# pca10040_sheet5_power_supply.net
KiCad netlist of a schematic drawn in Altium Designer
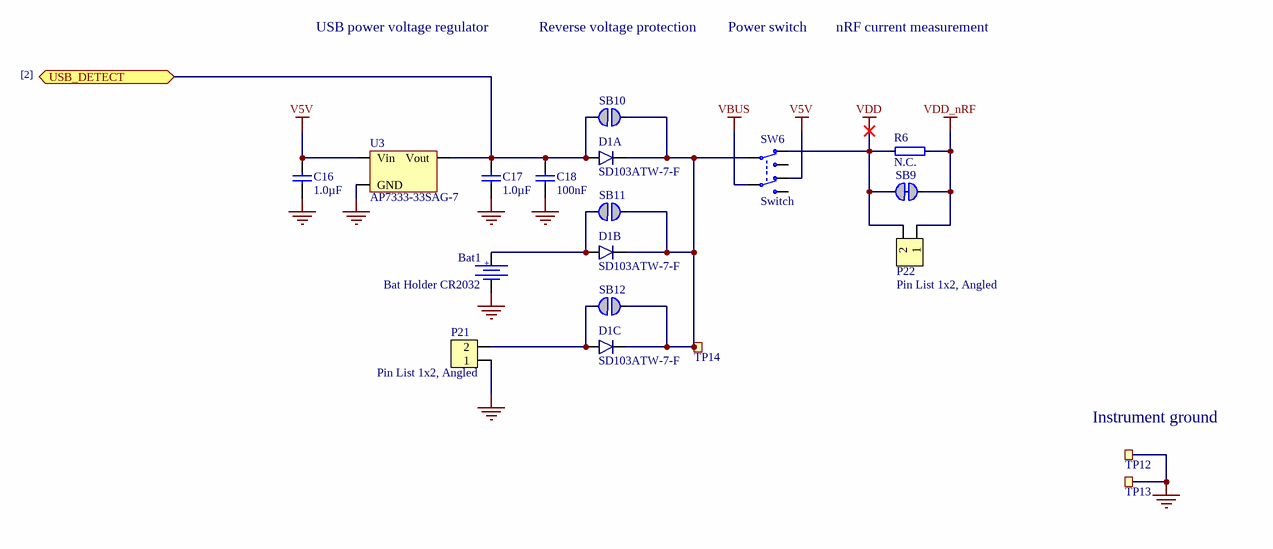
[diagram p0: pca10040_sheet5_power_supply.SchDoc]

(export (version "E")
  (design (tool "Eeschema 10.0.6"))
  (components
    (comp (ref "Bat1")
      (value "Bat Holder CR2032")
      (footprint "CR2032_HOLDER_SMD")
      (description "Bat Holder CR2032 SMD")
      (fields
        (field (name "MANUFACTURER") "Comfortable")
        (field (name "MANUFACTURER PART NUMBER") "BC-2001")
        (field (name "PUBLISHER") "Nordic Semiconductor")
      )
      (libsource (lib "Nordic Passive DB") (part "Battery"))
    )
    (comp (ref "C16")
      (value "1.0µF")
      (footprint "CAPC1608X06L")
      (description "Capacitor, X7R, ±10%")
      (fields (field (name "PART NUMBER") "C0603-1µ0") (field (name "PUBLISHER") "Nordic Semiconductor"))
      (libsource (lib "Nordic Passive DB") (part "CAP"))
    )
    (comp (ref "C17")
      (value "1.0µF")
      (footprint "CAPC1608X06L")
      (description "Capacitor, X7R, ±10%")
      (fields (field (name "PART NUMBER") "C0603-1µ0") (field (name "PUBLISHER") "Nordic Semiconductor"))
      (libsource (lib "Nordic Passive DB") (part "CAP"))
    )
    (comp (ref "C18")
      (value "100nF")
      (footprint "CAPC1005X04L")
      (description "Capacitor, X7R, ±10%")
      (fields (field (name "PART NUMBER") "C0402-100n") (field (name "PUBLISHER") "Nordic Semiconductor"))
      (libsource (lib "Nordic Passive DB") (part "CAP"))
    )
    (comp (ref "D1")
      (value "SD103ATW-7-F")
      (footprint "SOT-363")
      (description "Surface Mount Schottky Barrier Diode Array")
      (fields
        (field (name "MANUFACTURER") "Diodes Incorporated")
        (field (name "2ND SOURCE PART NUMBER") "177-3507")
        (field (name "PUBLISHER") "Nordic Semiconductor")
      )
      (libsource (lib "Nordic Discrete DB") (part "D{colon}DIODE_3_IND"))
    )
    (comp (ref "P21")
      (value "Pin List 1x2, Angled")
      (footprint "LIST_ANG_1x2-SMD-2.54MM")
      (description "Pin List 1x2, 2.54mm (100mil), Right Angled, SMD")
      (fields
        (field (name "PART NUMBER") "Pin List Ang 1x2 SMD, 2.54mm")
        (field (name "MANUFACTURER") "W-CON")
        (field (name "PUBLISHER") "Nordic Semiconductor")
      )
      (libsource (lib "Nordic Passive DB") (part "CONN-2"))
    )
    (comp (ref "P22")
      (value "Pin List 1x2, Angled")
      (footprint "LIST_ANG_1x2-SMD-2.54MM")
      (description "Pin List 1x2, 2.54mm (100mil), Right Angled, SMD")
      (fields
        (field (name "PART NUMBER") "Pin List Ang 1x2 SMD, 2.54mm")
        (field (name "MANUFACTURER") "W-CON")
        (field (name "PUBLISHER") "Nordic Semiconductor")
      )
      (libsource (lib "") (part "CONN-2_1"))
    )
    (comp (ref "R6")
      (value "N.C.")
      (footprint "RESC1005X04L")
      (description "Not mounted")
      (fields (field (name "PART NUMBER") "R0402-N.C.") (field (name "PUBLISHER") "Nordic Semiconductor"))
      (libsource (lib "Nordic Passive DB") (part "RES_1"))
    )
    (comp (ref "SB9")
      (value "Solderbridge")
      (footprint "Solderbridge_Shorted")
      (description "Shorted Solderbridge")
      (fields
        (field (name "PART NUMBER") "Solderbridge Shorted")
        (field (name "PUBLISHER") "Nordic Semiconductor")
      )
      (libsource (lib "Nordic Passive DB") (part "SOLDERBRIDGE_SHORTED"))
    )
    (comp (ref "SB10")
      (value "Solderbridge")
      (footprint "Solderbridge")
      (fields (field (name "PUBLISHER") "Nordic Semiconductor"))
      (libsource (lib "Nordic Passive DB") (part "SOLDERBRIDGE"))
    )
    (comp (ref "SB11")
      (value "Solderbridge")
      (footprint "Solderbridge")
      (fields (field (name "PUBLISHER") "Nordic Semiconductor"))
      (libsource (lib "Nordic Passive DB") (part "SOLDERBRIDGE"))
    )
    (comp (ref "SB12")
      (value "Solderbridge")
      (footprint "Solderbridge")
      (fields (field (name "PUBLISHER") "Nordic Semiconductor"))
      (libsource (lib "Nordic Passive DB") (part "SOLDERBRIDGE"))
    )
    (comp (ref "SW6")
      (value "Switch")
      (footprint "Switch-Slide-DPDT-8.5x3.6mm")
      (description "SMD slide Switch (ON-ON)")
      (fields
        (field (name "PART NUMBER") "Switch-Slide-DPDT-8.5x3.6mm")
        (field (name "MANUFACTURER") "Dailywell")
        (field (name "PUBLISHER") "Nordic Semiconductor")
      )
      (libsource (lib "Nordic Discrete DB") (part "SW-DPDT"))
    )
    (comp (ref "TP12")
      (value "TP")
      (footprint "TESTPAD-TH")
      (description "Testpoint, through hole")
      (fields (field (name "PART NUMBER") "Testpoint TH") (field (name "PUBLISHER") "Nordic Semiconductor"))
      (libsource (lib "") (part "TESTPAD_1"))
    )
    (comp (ref "TP13")
      (value "TP")
      (footprint "TESTPAD-TH")
      (description "Testpoint, through hole")
      (fields (field (name "PART NUMBER") "Testpoint TH") (field (name "PUBLISHER") "Nordic Semiconductor"))
      (libsource (lib "") (part "TESTPAD_1"))
    )
    (comp (ref "TP14")
      (value "Ø1.0mm,SMD")
      (footprint "TP_SMD_Ø1.0mm")
      (description "1.0mm circular SMD testpad")
      (fields
        (field (name "PART NUMBER") "TP_SMD_Ø1.0MM")
        (field (name "MANUFACTURER") "Nordic Semiconductor")
        (field (name "PUBLISHER") "Nordic Semiconductor")
      )
      (libsource (lib "Nordic Passive DB") (part "TESTPAD"))
    )
    (comp (ref "U3")
      (value "AP7333-33SAG-7")
      (footprint "SOT-23A")
      (description "300mA, Low Quiescent Current, Fast Transient Low Dropout Linear Regulator")
      (fields
        (field (name "MANUFACTURER") "Diodes Incorporated")
        (field (name "PUBLISHER") "Nordic Semiconductor")
      )
      (libsource (lib "Nordic Active DB") (part "AP7333-XXSAG"))
    )
  )
  (nets
    (net (code "1") (name "/USB_DETECT") (class "Default")
      (node (ref "C17") (pin "2") (pinfunction "2_2") (pintype "passive"))
      (node (ref "C18") (pin "2") (pinfunction "2_2") (pintype "passive"))
      (node (ref "D1") (pin "6") (pinfunction "A1_6") (pintype "passive"))
      (node (ref "SB10") (pin "2") (pinfunction "1_2") (pintype "passive"))
      (node (ref "U3") (pin "2") (pinfunction "Vout_2") (pintype "passive"))
    )
    (net (code "2") (name "GND") (class "Default")
      (node (ref "Bat1") (pin "2") (pintype "passive"))
      (node (ref "C16") (pin "1") (pinfunction "1_1") (pintype "passive"))
      (node (ref "C17") (pin "1") (pinfunction "1_1") (pintype "passive"))
      (node (ref "C18") (pin "1") (pinfunction "1_1") (pintype "passive"))
      (node (ref "P21") (pin "1") (pinfunction "1_1") (pintype "passive"))
      (node (ref "TP12") (pin "1") (pinfunction "1_1") (pintype "passive"))
      (node (ref "TP13") (pin "1") (pinfunction "1_1") (pintype "passive"))
      (node (ref "U3") (pin "3") (pinfunction "GND_3") (pintype "passive"))
    )
    (net (code "3") (name "Net-(D1A-C1)") (class "Default")
      (node (ref "D1") (pin "1") (pinfunction "C1_1") (pintype "passive"))
      (node (ref "D1") (pin "2") (pinfunction "C2_2") (pintype "passive"))
      (node (ref "D1") (pin "3") (pinfunction "C3_3") (pintype "passive"))
      (node (ref "SB10") (pin "1") (pinfunction "0_1") (pintype "passive"))
      (node (ref "SB11") (pin "1") (pinfunction "0_1") (pintype "passive"))
      (node (ref "SB12") (pin "1") (pinfunction "0_1") (pintype "passive"))
      (node (ref "SW6") (pin "2") (pinfunction "COM-1_2") (pintype "passive"))
      (node (ref "TP14") (pin "1") (pinfunction "1_1") (pintype "passive"))
    )
    (net (code "4") (name "Net-(D1B-A2)") (class "Default")
      (node (ref "Bat1") (pin "1") (pintype "passive"))
      (node (ref "D1") (pin "5") (pinfunction "A2_5") (pintype "passive"))
      (node (ref "SB11") (pin "2") (pinfunction "1_2") (pintype "passive"))
    )
    (net (code "5") (name "Net-(D1C-A3)") (class "Default")
      (node (ref "D1") (pin "4") (pinfunction "A3_4") (pintype "passive"))
      (node (ref "P21") (pin "2") (pinfunction "2_2") (pintype "passive"))
      (node (ref "SB12") (pin "2") (pinfunction "1_2") (pintype "passive"))
    )
    (net (code "6") (name "V5V") (class "Default")
      (node (ref "C16") (pin "2") (pinfunction "2_2") (pintype "passive"))
      (node (ref "SW6") (pin "6") (pinfunction "N.C-2_6") (pintype "passive"))
      (node (ref "U3") (pin "1") (pinfunction "Vin_1") (pintype "passive"))
    )
    (net (code "7") (name "VBUS") (class "Default")
      (node (ref "SW6") (pin "5") (pinfunction "COM-2_5") (pintype "passive"))
    )
    (net (code "8") (name "VDD") (class "Default")
      (node (ref "P22") (pin "2") (pinfunction "2_2") (pintype "passive"))
      (node (ref "R6") (pin "1") (pinfunction "1_1") (pintype "passive"))
      (node (ref "SB9") (pin "2") (pinfunction "1_2") (pintype "passive"))
      (node (ref "SW6") (pin "3") (pinfunction "N.C-1_3") (pintype "passive"))
    )
    (net (code "9") (name "VDD_nRF") (class "Default")
      (node (ref "P22") (pin "1") (pinfunction "1_1") (pintype "passive"))
      (node (ref "R6") (pin "2") (pinfunction "2_2") (pintype "passive"))
      (node (ref "SB9") (pin "1") (pinfunction "0_1") (pintype "passive"))
    )
    (net (code "10") (name "unconnected-(SW6-N.O-1-Pad1)") (class "Default")
      (node (ref "SW6") (pin "1") (pinfunction "N.O-1_1") (pintype "passive"))
    )
    (net (code "11") (name "unconnected-(SW6-N.O-2-Pad4)") (class "Default")
      (node (ref "SW6") (pin "4") (pinfunction "N.O-2_4") (pintype "passive"))
    )
  )
)
